# SHIEL_V1_0.net
KiCad netlist of a schematic drawn in EAGLE
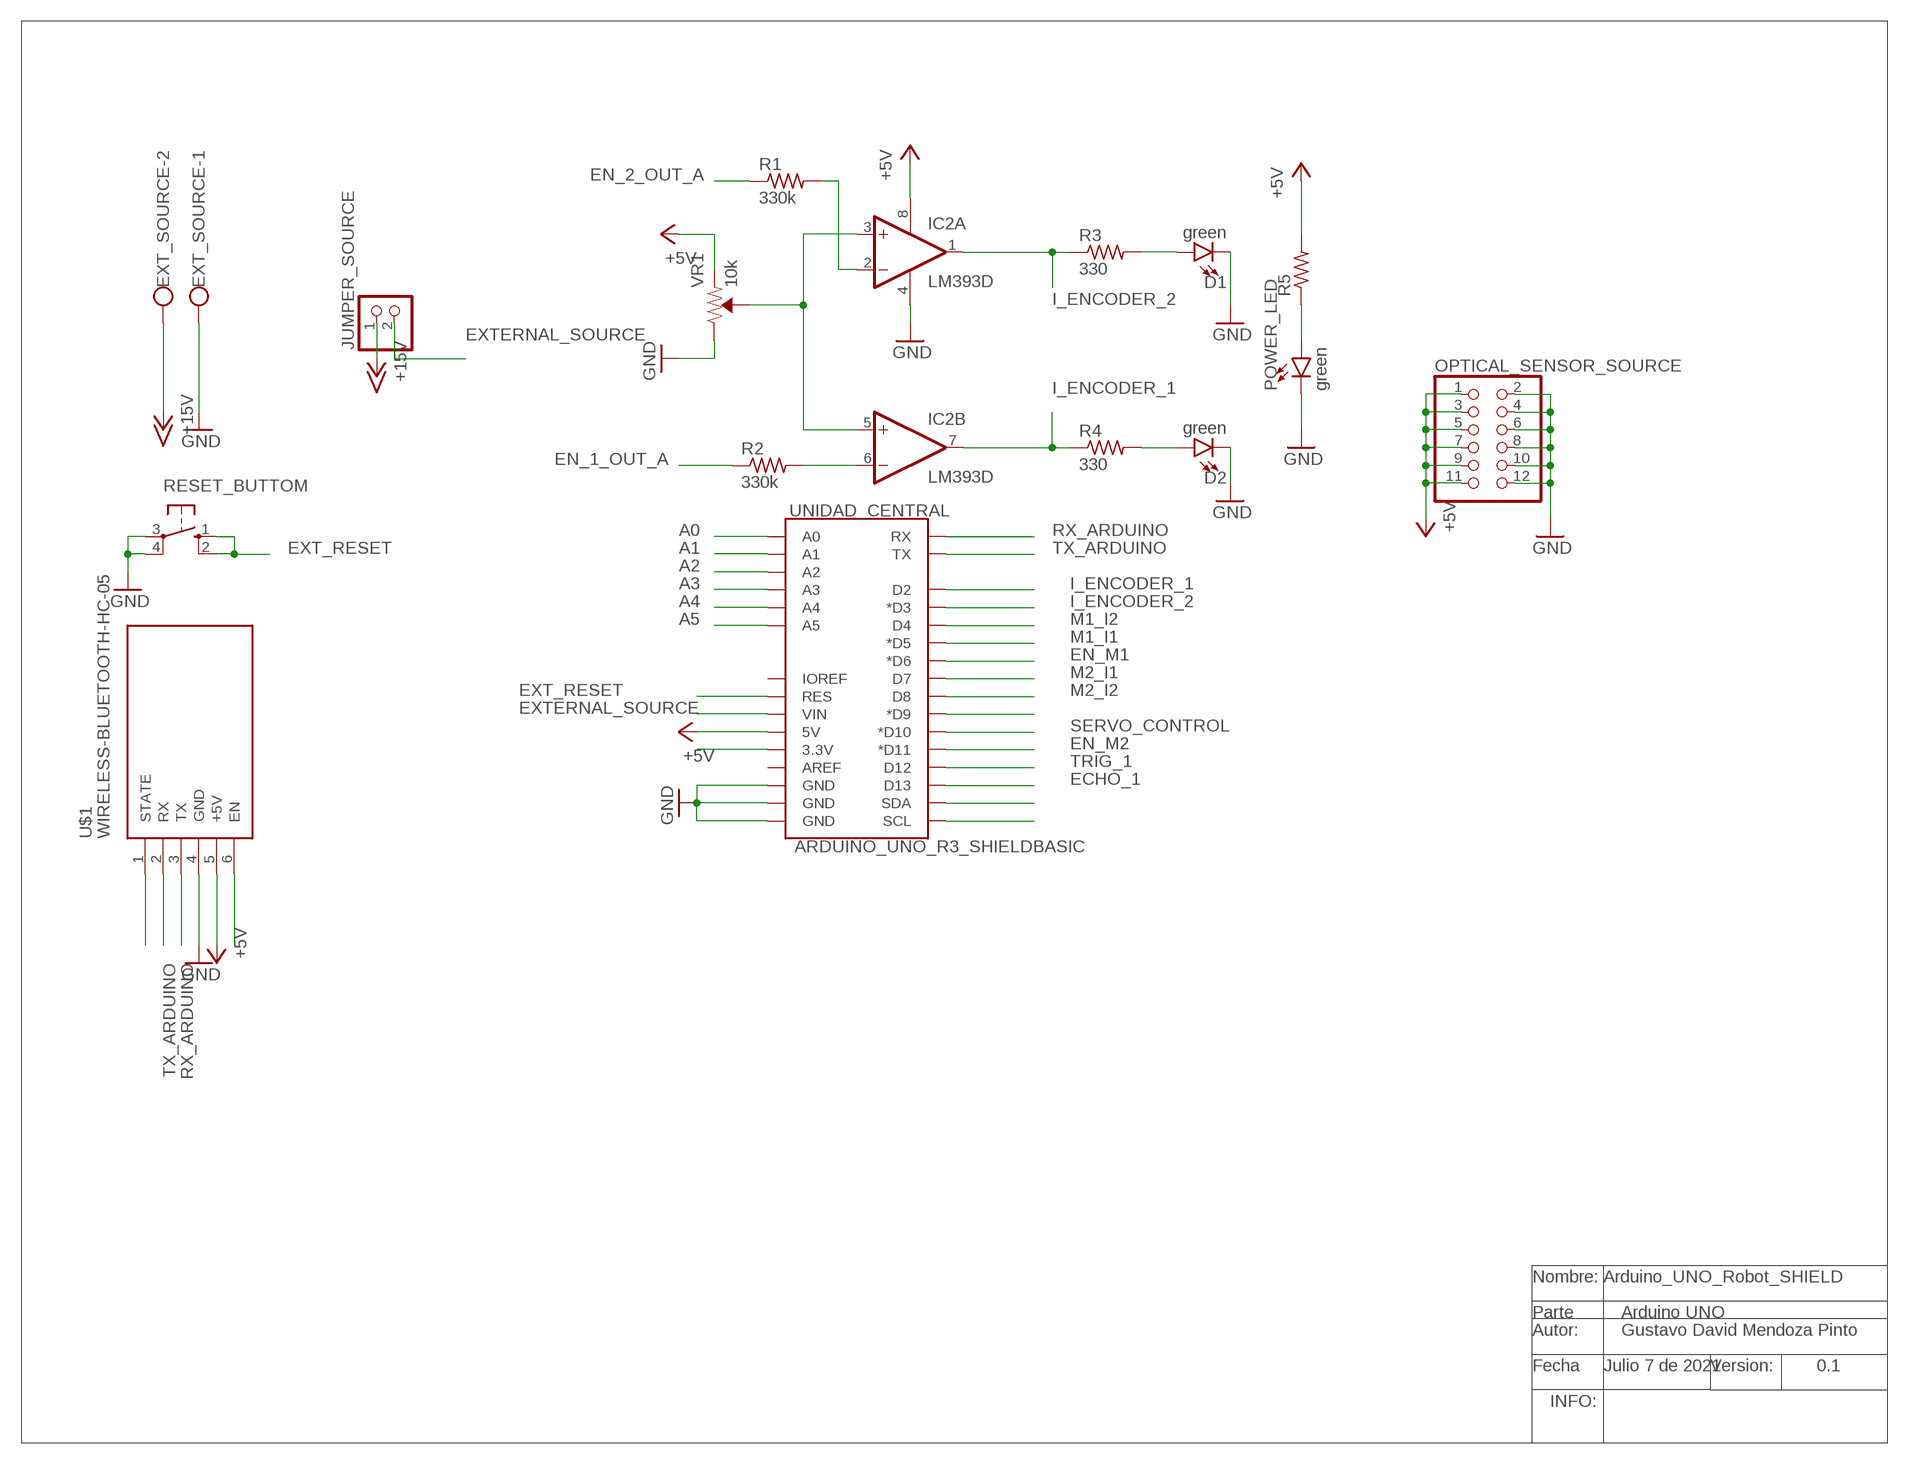
[diagram p0: schematic, sheet 1]
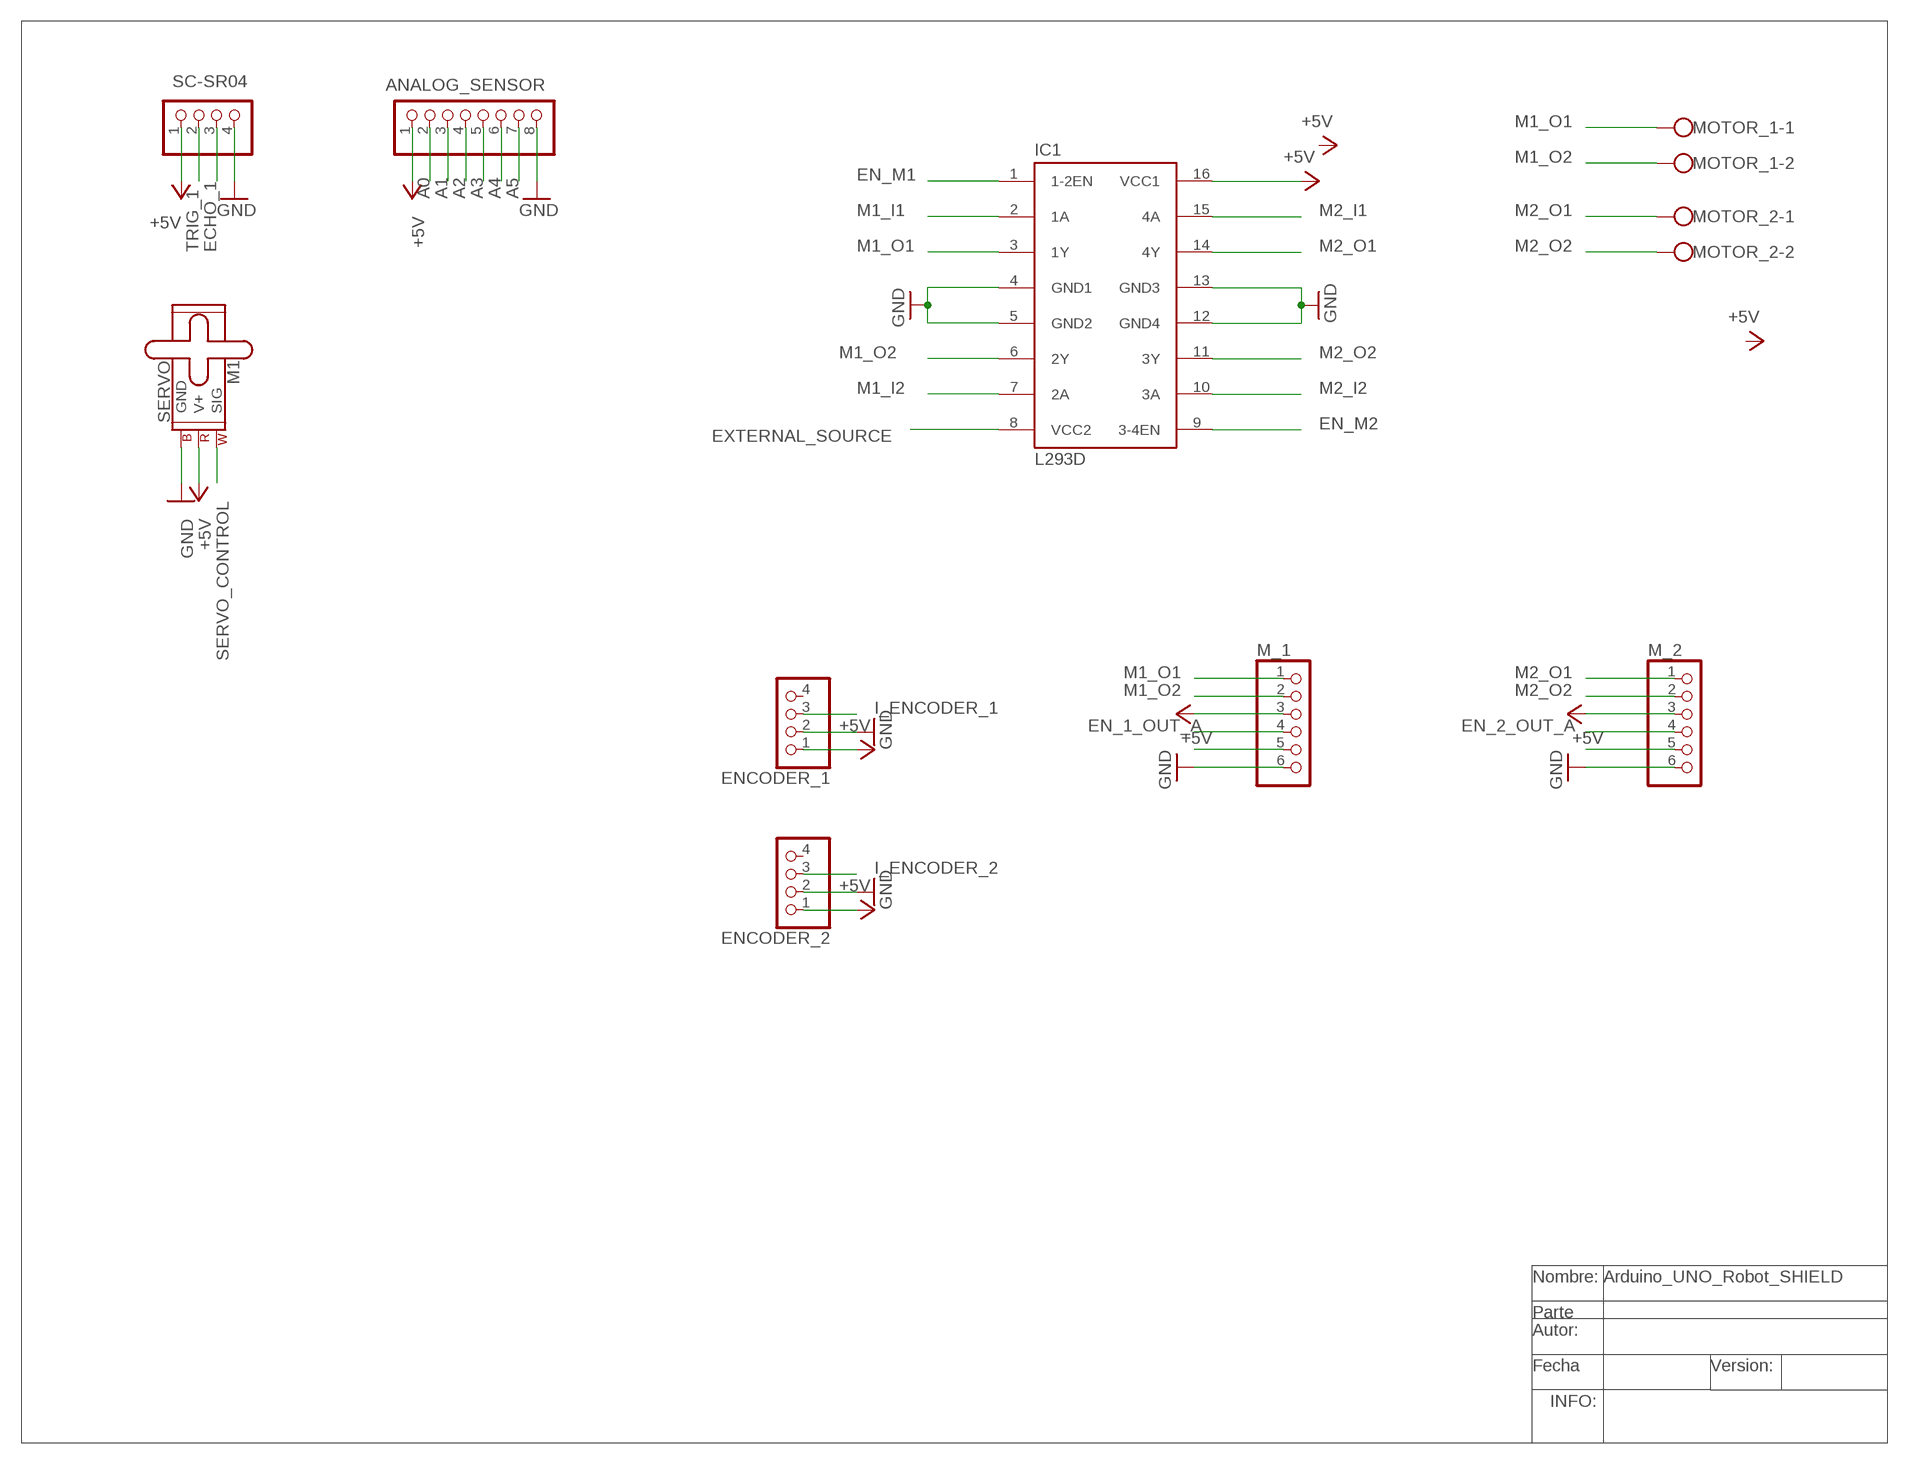
[diagram p1: schematic, sheet 2]

(export (version "E")
  (design (tool "Eeschema 10.0.6"))
  (components
    (comp (ref "ANALOG_SENSOR")
      (value "PINHD-1X8")
      (footprint "eagle-import:1X08")
      (libsource (lib "eagle-import") (part "PINHD-1X8"))
    )
    (comp (ref "ENCODER_1")
      (value "PINHD-1X4")
      (footprint "eagle-import:1X04")
      (libsource (lib "eagle-import") (part "PINHD-1X4"))
    )
    (comp (ref "ENCODER_2")
      (value "PINHD-1X4")
      (footprint "eagle-import:1X04")
      (libsource (lib "eagle-import") (part "PINHD-1X4"))
    )
    (comp (ref "IC1")
      (value "L293D")
      (footprint "eagle-import:DIL16")
      (libsource (lib "eagle-import") (part "L293D"))
    )
    (comp (ref "M1")
      (value "SERVO")
      (footprint "eagle-import:1X03")
      (libsource (lib "eagle-import") (part "SERVO"))
    )
    (comp (ref "MOTOR_1")
      (value "W237-102")
      (footprint "eagle-import:W237-102")
      (fields (field (name "MPN") "237-102"))
      (libsource (lib "eagle-import") (part "W237-102"))
    )
    (comp (ref "MOTOR_2")
      (value "W237-102")
      (footprint "eagle-import:W237-102")
      (fields (field (name "MPN") "237-102"))
      (libsource (lib "eagle-import") (part "W237-102"))
    )
    (comp (ref "M_1")
      (value "PINHD-1X6")
      (footprint "eagle-import:1X06")
      (libsource (lib "eagle-import") (part "PINHD-1X6"))
    )
    (comp (ref "M_2")
      (value "PINHD-1X6")
      (footprint "eagle-import:1X06")
      (libsource (lib "eagle-import") (part "PINHD-1X6"))
    )
    (comp (ref "SC-SR04")
      (value "PINHD-1X4")
      (footprint "eagle-import:1X04")
      (libsource (lib "eagle-import") (part "PINHD-1X4"))
    )
    (comp (ref "D1")
      (value "green")
      (footprint "eagle-import:LED_3MM-NS")
      (libsource (lib "eagle-import") (part "LED-3MM-NO_SILK"))
    )
    (comp (ref "D2")
      (value "green")
      (footprint "eagle-import:LED_3MM-NS")
      (libsource (lib "eagle-import") (part "LED-3MM-NO_SILK"))
    )
    (comp (ref "EXT_SOURCE")
      (value "W237-102")
      (footprint "eagle-import:W237-102")
      (fields (field (name "MPN") "237-102"))
      (libsource (lib "eagle-import") (part "W237-102"))
    )
    (comp (ref "IC2")
      (value "LM393D")
      (footprint "eagle-import:SO08")
      (libsource (lib "eagle-import") (part "LM393D"))
    )
    (comp (ref "JUMPER_SOURCE")
      (value "PINHD-1X2")
      (footprint "eagle-import:1X02")
      (libsource (lib "eagle-import") (part "PINHD-1X2"))
    )
    (comp (ref "OPTICAL_SENSOR_SOURCE")
      (value "PINHD-2X6")
      (footprint "eagle-import:2X06")
      (libsource (lib "eagle-import") (part "PINHD-2X6"))
    )
    (comp (ref "POWER_LED")
      (value "green")
      (footprint "eagle-import:LED_3MM-NS")
      (libsource (lib "eagle-import") (part "LED-3MM-NO_SILK"))
    )
    (comp (ref "R1")
      (value "330k")
      (footprint "eagle-import:M2012")
      (libsource (lib "eagle-import") (part "R-US_M2012"))
    )
    (comp (ref "R2")
      (value "330k")
      (footprint "eagle-import:M2012")
      (libsource (lib "eagle-import") (part "R-US_M2012"))
    )
    (comp (ref "R3")
      (value "330")
      (footprint "eagle-import:M2012")
      (libsource (lib "eagle-import") (part "R-US_M2012"))
    )
    (comp (ref "R4")
      (value "330")
      (footprint "eagle-import:M2012")
      (libsource (lib "eagle-import") (part "R-US_M2012"))
    )
    (comp (ref "R5")
      (value "R-US_M2012")
      (footprint "eagle-import:M2012")
      (libsource (lib "eagle-import") (part "R-US_M2012"))
    )
    (comp (ref "RESET_BUTTOM")
      (value "10-XX")
      (footprint "eagle-import:B3F-10XX")
      (fields (field (name "MPN") "B3F-1000"))
      (libsource (lib "eagle-import") (part "10-XX"))
    )
    (comp (ref "U$1")
      (value "WIRELESS-BLUETOOTH-HC-05")
      (footprint "eagle-import:WIRELESS-BLUETOOTH-HC-05")
      (libsource (lib "eagle-import") (part "WIRELESS-BLUETOOTH-HC-05"))
    )
    (comp (ref "UNIDAD_CENTRAL")
      (value "ARDUINO_UNO_R3_SHIELDBASIC")
      (footprint "eagle-import:UNO_R3_SHIELD")
      (libsource (lib "eagle-import") (part "ARDUINO_UNO_R3_SHIELDBASIC"))
    )
    (comp (ref "VR1")
      (value "10k")
      (footprint "eagle-import:TRIMPOT-PTH-3386U")
      (libsource (lib "eagle-import") (part "TRIMPOT-PTH-10MM-KNOB-1/2W-10%"))
    )
  )
  (nets
    (net (code "1") (name "+5V") (class "Default")
      (node (ref "ANALOG_SENSOR") (pin "1") (pinfunction "1_1") (pintype "passive"))
      (node (ref "ENCODER_1") (pin "1") (pinfunction "1_1") (pintype "passive"))
      (node (ref "ENCODER_2") (pin "1") (pinfunction "1_1") (pintype "passive"))
      (node (ref "IC1") (pin "16") (pinfunction "VCC1_16") (pintype "power_in"))
      (node (ref "IC2") (pin "8") (pinfunction "V+_8") (pintype "power_in"))
      (node (ref "M1") (pin "2") (pinfunction "V+_2") (pintype "bidirectional"))
      (node (ref "M_1") (pin "3") (pinfunction "3_3") (pintype "passive"))
      (node (ref "M_2") (pin "3") (pinfunction "3_3") (pintype "passive"))
      (node (ref "OPTICAL_SENSOR_SOURCE") (pin "1") (pinfunction "1_1") (pintype "passive"))
      (node (ref "OPTICAL_SENSOR_SOURCE") (pin "11") (pinfunction "11_11") (pintype "passive"))
      (node (ref "OPTICAL_SENSOR_SOURCE") (pin "3") (pinfunction "3_3") (pintype "passive"))
      (node (ref "OPTICAL_SENSOR_SOURCE") (pin "5") (pinfunction "5_5") (pintype "passive"))
      (node (ref "OPTICAL_SENSOR_SOURCE") (pin "7") (pinfunction "7_7") (pintype "passive"))
      (node (ref "OPTICAL_SENSOR_SOURCE") (pin "9") (pinfunction "9_9") (pintype "passive"))
      (node (ref "R5") (pin "2") (pinfunction "2_2") (pintype "passive"))
      (node (ref "SC-SR04") (pin "1") (pinfunction "1_1") (pintype "passive"))
      (node (ref "U$1") (pin "5") (pinfunction "+5V_5") (pintype "power_in"))
      (node (ref "UNIDAD_CENTRAL") (pin "5V") (pinfunction "5V_5V") (pintype "bidirectional"))
      (node (ref "VR1") (pin "1") (pinfunction "CCW_1") (pintype "passive"))
    )
    (net (code "2") (name "+15V") (class "Default")
      (node (ref "EXT_SOURCE") (pin "2") (pinfunction "KL_2") (pintype "passive"))
      (node (ref "JUMPER_SOURCE") (pin "1") (pinfunction "1_1") (pintype "passive"))
    )
    (net (code "3") (name "A0") (class "Default")
      (node (ref "ANALOG_SENSOR") (pin "2") (pinfunction "2_2") (pintype "passive"))
      (node (ref "UNIDAD_CENTRAL") (pin "A0") (pinfunction "A0_A0") (pintype "bidirectional"))
    )
    (net (code "4") (name "A1") (class "Default")
      (node (ref "ANALOG_SENSOR") (pin "3") (pinfunction "3_3") (pintype "passive"))
      (node (ref "UNIDAD_CENTRAL") (pin "A1") (pinfunction "A1_A1") (pintype "bidirectional"))
    )
    (net (code "5") (name "A2") (class "Default")
      (node (ref "ANALOG_SENSOR") (pin "4") (pinfunction "4_4") (pintype "passive"))
      (node (ref "UNIDAD_CENTRAL") (pin "A2") (pinfunction "A2_A2") (pintype "bidirectional"))
    )
    (net (code "6") (name "A3") (class "Default")
      (node (ref "ANALOG_SENSOR") (pin "5") (pinfunction "5_5") (pintype "passive"))
      (node (ref "UNIDAD_CENTRAL") (pin "A3") (pinfunction "A3_A3") (pintype "bidirectional"))
    )
    (net (code "7") (name "A4") (class "Default")
      (node (ref "ANALOG_SENSOR") (pin "6") (pinfunction "6_6") (pintype "passive"))
      (node (ref "UNIDAD_CENTRAL") (pin "A4") (pinfunction "A4_A4") (pintype "bidirectional"))
    )
    (net (code "8") (name "A5") (class "Default")
      (node (ref "ANALOG_SENSOR") (pin "7") (pinfunction "7_7") (pintype "passive"))
      (node (ref "UNIDAD_CENTRAL") (pin "A5") (pinfunction "A5_A5") (pintype "bidirectional"))
    )
    (net (code "9") (name "ECHO_1") (class "Default")
      (node (ref "SC-SR04") (pin "3") (pinfunction "3_3") (pintype "passive"))
      (node (ref "UNIDAD_CENTRAL") (pin "D13") (pinfunction "D13_D13") (pintype "bidirectional"))
    )
    (net (code "10") (name "EN_1_OUT_A") (class "Default")
      (node (ref "M_1") (pin "4") (pinfunction "4_4") (pintype "passive"))
      (node (ref "R2") (pin "1") (pinfunction "1_1") (pintype "passive"))
    )
    (net (code "11") (name "EN_2_OUT_A") (class "Default")
      (node (ref "M_2") (pin "4") (pinfunction "4_4") (pintype "passive"))
      (node (ref "R1") (pin "1") (pinfunction "1_1") (pintype "passive"))
    )
    (net (code "12") (name "EN_M1") (class "Default")
      (node (ref "IC1") (pin "1") (pinfunction "1-2EN_1") (pintype "input"))
      (node (ref "UNIDAD_CENTRAL") (pin "D6") (pinfunction "*D6_D6") (pintype "bidirectional"))
    )
    (net (code "13") (name "EN_M2") (class "Default")
      (node (ref "IC1") (pin "9") (pinfunction "3-4EN_9") (pintype "input"))
      (node (ref "UNIDAD_CENTRAL") (pin "D11") (pinfunction "*D11_D11") (pintype "bidirectional"))
    )
    (net (code "14") (name "EXTERNAL_SOURCE") (class "Default")
      (node (ref "IC1") (pin "8") (pinfunction "VCC2_8") (pintype "power_in"))
      (node (ref "JUMPER_SOURCE") (pin "2") (pinfunction "2_2") (pintype "passive"))
      (node (ref "UNIDAD_CENTRAL") (pin "VIN") (pinfunction "VIN_VIN") (pintype "bidirectional"))
    )
    (net (code "15") (name "EXT_RESET") (class "Default")
      (node (ref "RESET_BUTTOM") (pin "1") (pinfunction "S_1") (pintype "passive"))
      (node (ref "RESET_BUTTOM") (pin "2") (pinfunction "S1_2") (pintype "passive"))
      (node (ref "UNIDAD_CENTRAL") (pin "RES") (pinfunction "RES_RES") (pintype "bidirectional"))
    )
    (net (code "16") (name "GND") (class "Default")
      (node (ref "ANALOG_SENSOR") (pin "8") (pinfunction "8_8") (pintype "passive"))
      (node (ref "D1") (pin "K") (pinfunction "C_K") (pintype "passive"))
      (node (ref "D2") (pin "K") (pinfunction "C_K") (pintype "passive"))
      (node (ref "ENCODER_1") (pin "2") (pinfunction "2_2") (pintype "passive"))
      (node (ref "ENCODER_2") (pin "2") (pinfunction "2_2") (pintype "passive"))
      (node (ref "EXT_SOURCE") (pin "1") (pinfunction "KL_1") (pintype "passive"))
      (node (ref "IC1") (pin "12") (pinfunction "GND4_12") (pintype "power_in"))
      (node (ref "IC1") (pin "13") (pinfunction "GND3_13") (pintype "power_in"))
      (node (ref "IC1") (pin "4") (pinfunction "GND1_4") (pintype "power_in"))
      (node (ref "IC1") (pin "5") (pinfunction "GND2_5") (pintype "power_in"))
      (node (ref "IC2") (pin "4") (pinfunction "V-_4") (pintype "power_in"))
      (node (ref "M1") (pin "3") (pinfunction "GND_3") (pintype "bidirectional"))
      (node (ref "M_1") (pin "6") (pinfunction "6_6") (pintype "passive"))
      (node (ref "M_2") (pin "6") (pinfunction "6_6") (pintype "passive"))
      (node (ref "OPTICAL_SENSOR_SOURCE") (pin "10") (pinfunction "10_10") (pintype "passive"))
      (node (ref "OPTICAL_SENSOR_SOURCE") (pin "12") (pinfunction "12_12") (pintype "passive"))
      (node (ref "OPTICAL_SENSOR_SOURCE") (pin "2") (pinfunction "2_2") (pintype "passive"))
      (node (ref "OPTICAL_SENSOR_SOURCE") (pin "4") (pinfunction "4_4") (pintype "passive"))
      (node (ref "OPTICAL_SENSOR_SOURCE") (pin "6") (pinfunction "6_6") (pintype "passive"))
      (node (ref "OPTICAL_SENSOR_SOURCE") (pin "8") (pinfunction "8_8") (pintype "passive"))
      (node (ref "POWER_LED") (pin "K") (pinfunction "C_K") (pintype "passive"))
      (node (ref "RESET_BUTTOM") (pin "3") (pinfunction "P_3") (pintype "passive"))
      (node (ref "RESET_BUTTOM") (pin "4") (pinfunction "P1_4") (pintype "passive"))
      (node (ref "SC-SR04") (pin "4") (pinfunction "4_4") (pintype "passive"))
      (node (ref "U$1") (pin "4") (pinfunction "GND_4") (pintype "power_in"))
      (node (ref "UNIDAD_CENTRAL") (pin "GND@0") (pinfunction "GND_GND@0") (pintype "bidirectional"))
      (node (ref "UNIDAD_CENTRAL") (pin "GND@1") (pinfunction "GND_GND@1") (pintype "bidirectional"))
      (node (ref "UNIDAD_CENTRAL") (pin "GND@2") (pinfunction "GND_GND@2") (pintype "bidirectional"))
      (node (ref "VR1") (pin "3") (pinfunction "CW_3") (pintype "passive"))
    )
    (net (code "17") (name "I_ENCODER_1") (class "Default")
      (node (ref "ENCODER_1") (pin "3") (pinfunction "3_3") (pintype "passive"))
      (node (ref "IC2") (pin "7") (pinfunction "OUT_7") (pintype "output"))
      (node (ref "R4") (pin "1") (pinfunction "1_1") (pintype "passive"))
      (node (ref "UNIDAD_CENTRAL") (pin "D2") (pinfunction "D2_D2") (pintype "bidirectional"))
    )
    (net (code "18") (name "I_ENCODER_2") (class "Default")
      (node (ref "ENCODER_2") (pin "3") (pinfunction "3_3") (pintype "passive"))
      (node (ref "IC2") (pin "1") (pinfunction "OUT_1") (pintype "output"))
      (node (ref "R3") (pin "1") (pinfunction "1_1") (pintype "passive"))
      (node (ref "UNIDAD_CENTRAL") (pin "D3") (pinfunction "*D3_D3") (pintype "bidirectional"))
    )
    (net (code "19") (name "M1_I1") (class "Default")
      (node (ref "IC1") (pin "2") (pinfunction "1A_2") (pintype "input"))
      (node (ref "UNIDAD_CENTRAL") (pin "D5") (pinfunction "*D5_D5") (pintype "bidirectional"))
    )
    (net (code "20") (name "M1_I2") (class "Default")
      (node (ref "IC1") (pin "7") (pinfunction "2A_7") (pintype "input"))
      (node (ref "UNIDAD_CENTRAL") (pin "D4") (pinfunction "D4_D4") (pintype "bidirectional"))
    )
    (net (code "21") (name "M1_O1") (class "Default")
      (node (ref "IC1") (pin "3") (pinfunction "1Y_3") (pintype "output"))
      (node (ref "MOTOR_1") (pin "1") (pinfunction "KL_1") (pintype "passive"))
      (node (ref "M_1") (pin "1") (pinfunction "1_1") (pintype "passive"))
    )
    (net (code "22") (name "M1_O2") (class "Default")
      (node (ref "IC1") (pin "6") (pinfunction "2Y_6") (pintype "output"))
      (node (ref "MOTOR_1") (pin "2") (pinfunction "KL_2") (pintype "passive"))
      (node (ref "M_1") (pin "2") (pinfunction "2_2") (pintype "passive"))
    )
    (net (code "23") (name "M2_I1") (class "Default")
      (node (ref "IC1") (pin "15") (pinfunction "4A_15") (pintype "input"))
      (node (ref "UNIDAD_CENTRAL") (pin "D7") (pinfunction "D7_D7") (pintype "bidirectional"))
    )
    (net (code "24") (name "M2_I2") (class "Default")
      (node (ref "IC1") (pin "10") (pinfunction "3A_10") (pintype "input"))
      (node (ref "UNIDAD_CENTRAL") (pin "D8") (pinfunction "D8_D8") (pintype "bidirectional"))
    )
    (net (code "25") (name "M2_O1") (class "Default")
      (node (ref "IC1") (pin "14") (pinfunction "4Y_14") (pintype "output"))
      (node (ref "MOTOR_2") (pin "1") (pinfunction "KL_1") (pintype "passive"))
      (node (ref "M_2") (pin "1") (pinfunction "1_1") (pintype "passive"))
    )
    (net (code "26") (name "M2_O2") (class "Default")
      (node (ref "IC1") (pin "11") (pinfunction "3Y_11") (pintype "output"))
      (node (ref "MOTOR_2") (pin "2") (pinfunction "KL_2") (pintype "passive"))
      (node (ref "M_2") (pin "2") (pinfunction "2_2") (pintype "passive"))
    )
    (net (code "27") (name "Net-(D1-PadA)") (class "Default")
      (node (ref "D1") (pin "A") (pinfunction "A_A") (pintype "passive"))
      (node (ref "R3") (pin "2") (pinfunction "2_2") (pintype "passive"))
    )
    (net (code "28") (name "Net-(D2-PadA)") (class "Default")
      (node (ref "D2") (pin "A") (pinfunction "A_A") (pintype "passive"))
      (node (ref "R4") (pin "2") (pinfunction "2_2") (pintype "passive"))
    )
    (net (code "29") (name "Net-(IC2A-+IN)") (class "Default")
      (node (ref "IC2") (pin "3") (pinfunction "+IN_3") (pintype "input"))
      (node (ref "IC2") (pin "5") (pinfunction "+IN_5") (pintype "input"))
      (node (ref "VR1") (pin "2") (pinfunction "WIPER_2") (pintype "passive"))
    )
    (net (code "30") (name "Net-(IC2A--IN)") (class "Default")
      (node (ref "IC2") (pin "2") (pinfunction "-IN_2") (pintype "input"))
      (node (ref "R1") (pin "2") (pinfunction "2_2") (pintype "passive"))
    )
    (net (code "31") (name "Net-(IC2B--IN)") (class "Default")
      (node (ref "IC2") (pin "6") (pinfunction "-IN_6") (pintype "input"))
      (node (ref "R2") (pin "2") (pinfunction "2_2") (pintype "passive"))
    )
    (net (code "32") (name "Net-(POWER_LED-PadA)") (class "Default")
      (node (ref "POWER_LED") (pin "A") (pinfunction "A_A") (pintype "passive"))
      (node (ref "R5") (pin "1") (pinfunction "1_1") (pintype "passive"))
    )
    (net (code "33") (name "RX_ARDUINO") (class "Default")
      (node (ref "U$1") (pin "3") (pinfunction "TX_3") (pintype "bidirectional"))
      (node (ref "UNIDAD_CENTRAL") (pin "RX") (pinfunction "RX_RX") (pintype "bidirectional"))
    )
    (net (code "34") (name "SERVO_CONTROL") (class "Default")
      (node (ref "M1") (pin "1") (pinfunction "SIG_1") (pintype "bidirectional"))
      (node (ref "UNIDAD_CENTRAL") (pin "D10") (pinfunction "*D10_D10") (pintype "bidirectional"))
    )
    (net (code "35") (name "TRIG_1") (class "Default")
      (node (ref "SC-SR04") (pin "2") (pinfunction "2_2") (pintype "passive"))
      (node (ref "UNIDAD_CENTRAL") (pin "D12") (pinfunction "D12_D12") (pintype "bidirectional"))
    )
    (net (code "36") (name "TX_ARDUINO") (class "Default")
      (node (ref "U$1") (pin "2") (pinfunction "RX_2") (pintype "bidirectional"))
      (node (ref "UNIDAD_CENTRAL") (pin "TX") (pinfunction "TX_TX") (pintype "bidirectional"))
    )
    (net (code "37") (name "unconnected-(ENCODER_1-Pad4)") (class "Default")
      (node (ref "ENCODER_1") (pin "4") (pinfunction "4_4") (pintype "passive"))
    )
    (net (code "38") (name "unconnected-(ENCODER_2-Pad4)") (class "Default")
      (node (ref "ENCODER_2") (pin "4") (pinfunction "4_4") (pintype "passive"))
    )
    (net (code "39") (name "unconnected-(M_1-Pad5)") (class "Default")
      (node (ref "M_1") (pin "5") (pinfunction "5_5") (pintype "passive"))
    )
    (net (code "40") (name "unconnected-(M_2-Pad5)") (class "Default")
      (node (ref "M_2") (pin "5") (pinfunction "5_5") (pintype "passive"))
    )
    (net (code "41") (name "unconnected-(U$1-EN-Pad6)") (class "Default")
      (node (ref "U$1") (pin "6") (pinfunction "EN_6") (pintype "bidirectional"))
    )
    (net (code "42") (name "unconnected-(U$1-STATE-Pad1)") (class "Default")
      (node (ref "U$1") (pin "1") (pinfunction "STATE_1") (pintype "bidirectional"))
    )
    (net (code "43") (name "unconnected-(UNIDAD_CENTRAL-*D9-PadD9)") (class "Default")
      (node (ref "UNIDAD_CENTRAL") (pin "D9") (pinfunction "*D9_D9") (pintype "bidirectional"))
    )
    (net (code "44") (name "unconnected-(UNIDAD_CENTRAL-Pad3.3V)") (class "Default")
      (node (ref "UNIDAD_CENTRAL") (pin "3.3V") (pinfunction "3.3V_3.3V") (pintype "bidirectional"))
    )
    (net (code "45") (name "unconnected-(UNIDAD_CENTRAL-PadAREF)") (class "Default")
      (node (ref "UNIDAD_CENTRAL") (pin "AREF") (pinfunction "AREF_AREF") (pintype "bidirectional"))
    )
    (net (code "46") (name "unconnected-(UNIDAD_CENTRAL-PadIOREF)") (class "Default")
      (node (ref "UNIDAD_CENTRAL") (pin "IOREF") (pinfunction "IOREF_IOREF") (pintype "bidirectional"))
    )
    (net (code "47") (name "unconnected-(UNIDAD_CENTRAL-PadSCL)") (class "Default")
      (node (ref "UNIDAD_CENTRAL") (pin "SCL") (pinfunction "SCL_SCL") (pintype "bidirectional"))
    )
    (net (code "48") (name "unconnected-(UNIDAD_CENTRAL-PadSDA)") (class "Default")
      (node (ref "UNIDAD_CENTRAL") (pin "SDA") (pinfunction "SDA_SDA") (pintype "bidirectional"))
    )
  )
)
